# CAN_Funktionsdecoder.net
KiCad netlist of a schematic drawn in EAGLE
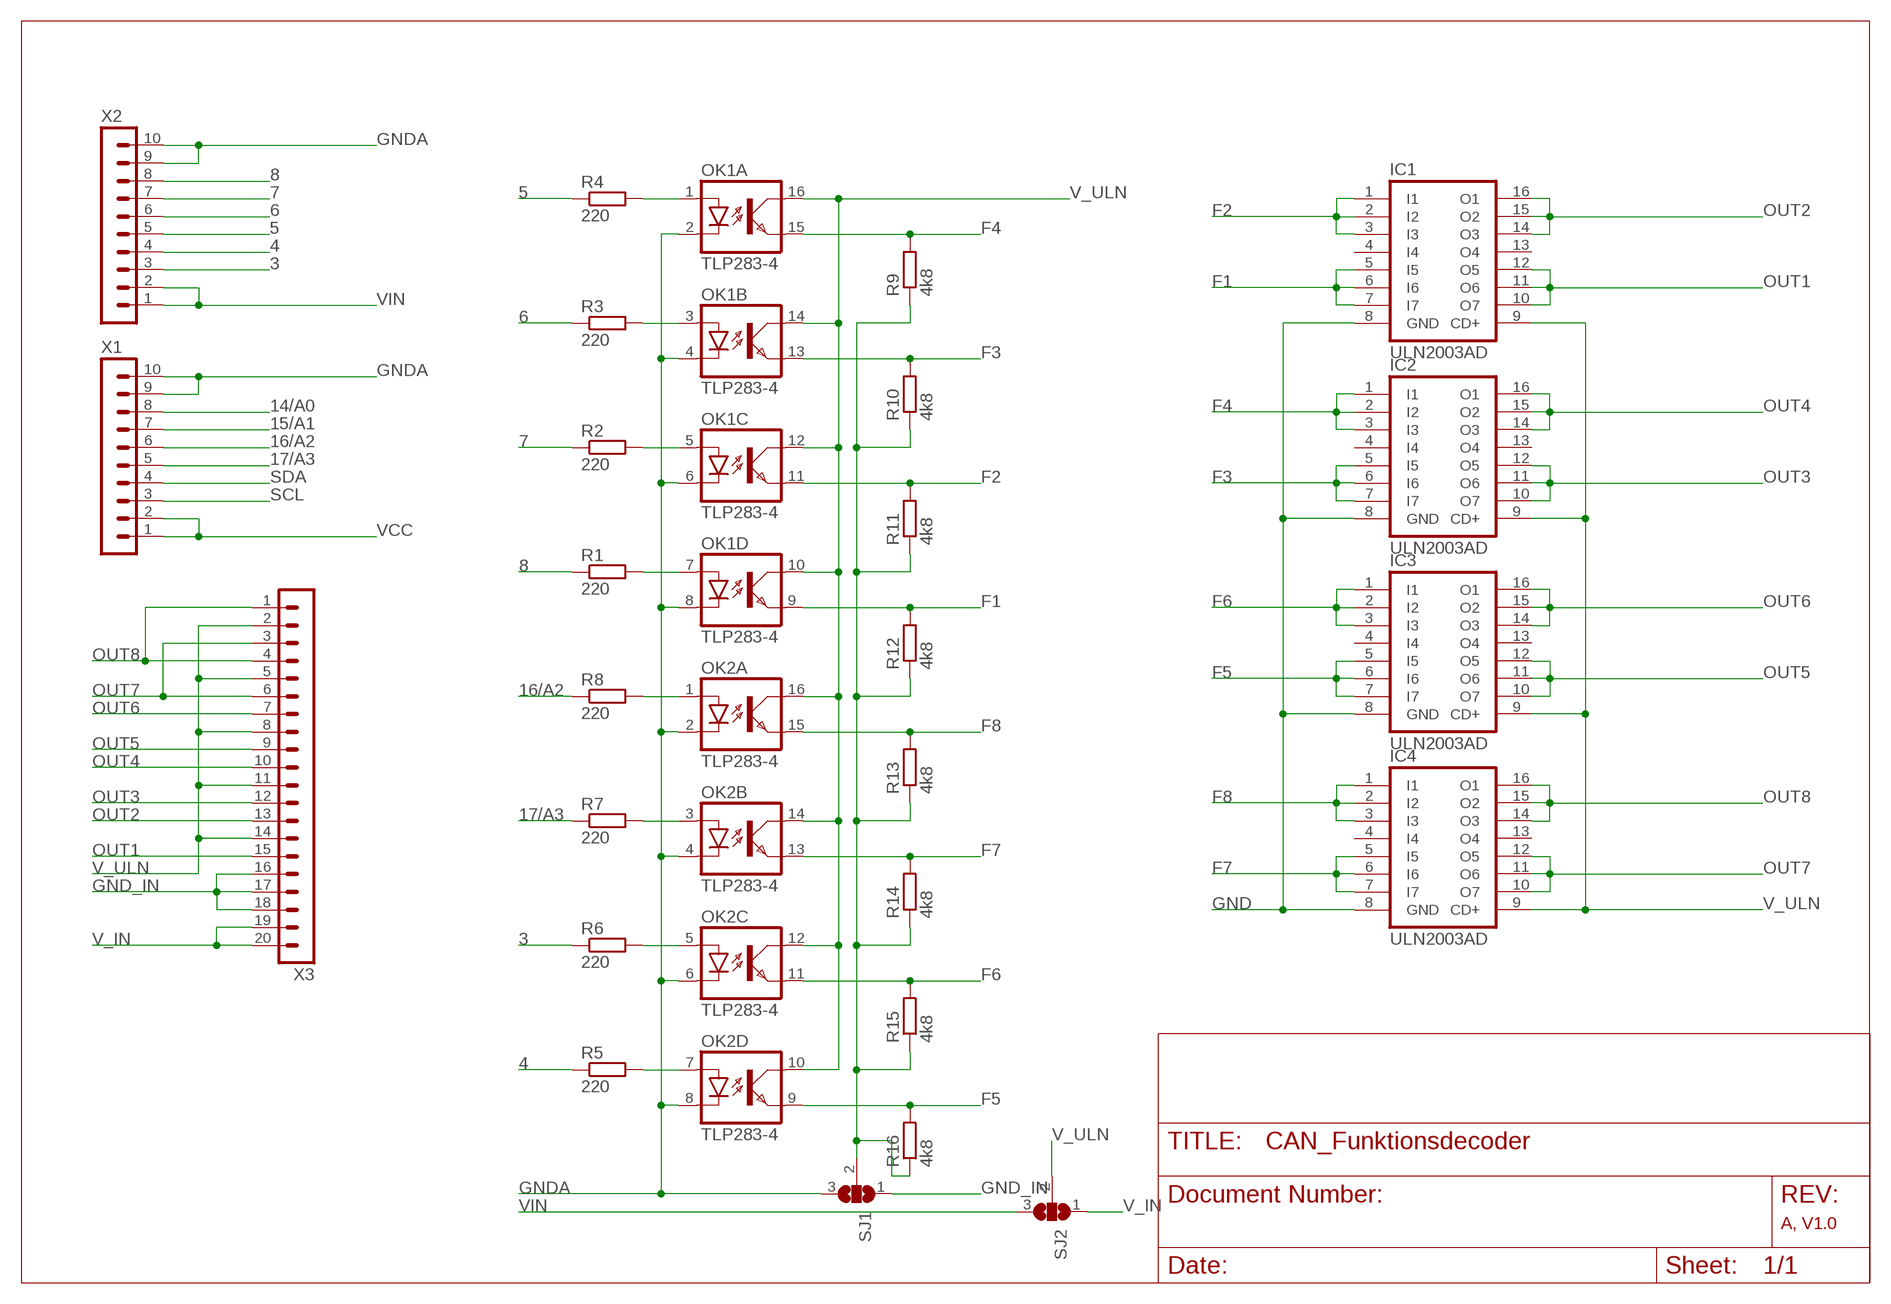
[diagram p0: schematic, sheet 1]

(export (version "E")
  (design (tool "Eeschema 10.0.6"))
  (components
    (comp (ref "IC1")
      (value "ULN2003AD")
      (footprint "eagle-import:SO16")
      (libsource (lib "eagle-import") (part "ULN2003AD"))
    )
    (comp (ref "IC2")
      (value "ULN2003AD")
      (footprint "eagle-import:SO16")
      (libsource (lib "eagle-import") (part "ULN2003AD"))
    )
    (comp (ref "IC3")
      (value "ULN2003AD")
      (footprint "eagle-import:SO16")
      (libsource (lib "eagle-import") (part "ULN2003AD"))
    )
    (comp (ref "IC4")
      (value "ULN2003AD")
      (footprint "eagle-import:SO16")
      (libsource (lib "eagle-import") (part "ULN2003AD"))
    )
    (comp (ref "OK1")
      (value "TLP283-4")
      (footprint "eagle-import:MINI-FLAT-16")
      (libsource (lib "eagle-import") (part "TLP283-4"))
    )
    (comp (ref "OK2")
      (value "TLP283-4")
      (footprint "eagle-import:MINI-FLAT-16")
      (libsource (lib "eagle-import") (part "TLP283-4"))
    )
    (comp (ref "R1")
      (value "220")
      (footprint "eagle-import:R0805")
      (libsource (lib "eagle-import") (part "R-EU_R0805"))
    )
    (comp (ref "R2")
      (value "220")
      (footprint "eagle-import:R0805")
      (libsource (lib "eagle-import") (part "R-EU_R0805"))
    )
    (comp (ref "R3")
      (value "220")
      (footprint "eagle-import:R0805")
      (libsource (lib "eagle-import") (part "R-EU_R0805"))
    )
    (comp (ref "R4")
      (value "220")
      (footprint "eagle-import:R0805")
      (libsource (lib "eagle-import") (part "R-EU_R0805"))
    )
    (comp (ref "R5")
      (value "220")
      (footprint "eagle-import:R0805")
      (libsource (lib "eagle-import") (part "R-EU_R0805"))
    )
    (comp (ref "R6")
      (value "220")
      (footprint "eagle-import:R0805")
      (libsource (lib "eagle-import") (part "R-EU_R0805"))
    )
    (comp (ref "R7")
      (value "220")
      (footprint "eagle-import:R0805")
      (libsource (lib "eagle-import") (part "R-EU_R0805"))
    )
    (comp (ref "R8")
      (value "220")
      (footprint "eagle-import:R0805")
      (libsource (lib "eagle-import") (part "R-EU_R0805"))
    )
    (comp (ref "R9")
      (value "4k8")
      (footprint "eagle-import:R0805")
      (libsource (lib "eagle-import") (part "R-EU_R0805"))
    )
    (comp (ref "R10")
      (value "4k8")
      (footprint "eagle-import:R0805")
      (libsource (lib "eagle-import") (part "R-EU_R0805"))
    )
    (comp (ref "R11")
      (value "4k8")
      (footprint "eagle-import:R0805")
      (libsource (lib "eagle-import") (part "R-EU_R0805"))
    )
    (comp (ref "R12")
      (value "4k8")
      (footprint "eagle-import:R0805")
      (libsource (lib "eagle-import") (part "R-EU_R0805"))
    )
    (comp (ref "R13")
      (value "4k8")
      (footprint "eagle-import:R0805")
      (libsource (lib "eagle-import") (part "R-EU_R0805"))
    )
    (comp (ref "R14")
      (value "4k8")
      (footprint "eagle-import:R0805")
      (libsource (lib "eagle-import") (part "R-EU_R0805"))
    )
    (comp (ref "R15")
      (value "4k8")
      (footprint "eagle-import:R0805")
      (libsource (lib "eagle-import") (part "R-EU_R0805"))
    )
    (comp (ref "R16")
      (value "4k8")
      (footprint "eagle-import:R0805")
      (libsource (lib "eagle-import") (part "R-EU_R0805"))
    )
    (comp (ref "SJ1")
      (value "SJ2W")
      (footprint "eagle-import:SJ_2")
      (libsource (lib "eagle-import") (part "SJ2W"))
    )
    (comp (ref "SJ2")
      (value "SJ2W")
      (footprint "eagle-import:SJ_2")
      (libsource (lib "eagle-import") (part "SJ2W"))
    )
    (comp (ref "X1")
      (value "MA10-1")
      (footprint "eagle-import:MA10-1")
      (libsource (lib "eagle-import") (part "MA10-1"))
    )
    (comp (ref "X2")
      (value "MA10-1")
      (footprint "eagle-import:MA10-1")
      (libsource (lib "eagle-import") (part "MA10-1"))
    )
    (comp (ref "X3")
      (value "MA20-1")
      (footprint "eagle-import:MA20-1")
      (libsource (lib "eagle-import") (part "MA20-1"))
    )
  )
  (nets
    (net (code "1") (name "/3") (class "Default")
      (node (ref "R6") (pin "1") (pinfunction "1_1") (pintype "passive"))
      (node (ref "X2") (pin "3") (pinfunction "3_3") (pintype "passive"))
    )
    (net (code "2") (name "/4") (class "Default")
      (node (ref "R5") (pin "1") (pinfunction "1_1") (pintype "passive"))
      (node (ref "X2") (pin "4") (pinfunction "4_4") (pintype "passive"))
    )
    (net (code "3") (name "/5") (class "Default")
      (node (ref "R4") (pin "1") (pinfunction "1_1") (pintype "passive"))
      (node (ref "X2") (pin "5") (pinfunction "5_5") (pintype "passive"))
    )
    (net (code "4") (name "/6") (class "Default")
      (node (ref "R3") (pin "1") (pinfunction "1_1") (pintype "passive"))
      (node (ref "X2") (pin "6") (pinfunction "6_6") (pintype "passive"))
    )
    (net (code "5") (name "/7") (class "Default")
      (node (ref "R2") (pin "1") (pinfunction "1_1") (pintype "passive"))
      (node (ref "X2") (pin "7") (pinfunction "7_7") (pintype "passive"))
    )
    (net (code "6") (name "/8") (class "Default")
      (node (ref "R1") (pin "1") (pinfunction "1_1") (pintype "passive"))
      (node (ref "X2") (pin "8") (pinfunction "8_8") (pintype "passive"))
    )
    (net (code "7") (name "/14{slash}A0") (class "Default")
      (node (ref "X1") (pin "8") (pinfunction "8_8") (pintype "passive"))
    )
    (net (code "8") (name "/15{slash}A1") (class "Default")
      (node (ref "X1") (pin "7") (pinfunction "7_7") (pintype "passive"))
    )
    (net (code "9") (name "/16{slash}A2") (class "Default")
      (node (ref "R8") (pin "1") (pinfunction "1_1") (pintype "passive"))
      (node (ref "X1") (pin "6") (pinfunction "6_6") (pintype "passive"))
    )
    (net (code "10") (name "/17{slash}A3") (class "Default")
      (node (ref "R7") (pin "1") (pinfunction "1_1") (pintype "passive"))
      (node (ref "X1") (pin "5") (pinfunction "5_5") (pintype "passive"))
    )
    (net (code "11") (name "/F1") (class "Default")
      (node (ref "IC1") (pin "5") (pinfunction "I5_5") (pintype "input"))
      (node (ref "IC1") (pin "6") (pinfunction "I6_6") (pintype "input"))
      (node (ref "IC1") (pin "7") (pinfunction "I7_7") (pintype "input"))
      (node (ref "OK1") (pin "9") (pinfunction "EMIT_9") (pintype "passive"))
      (node (ref "R12") (pin "2") (pinfunction "2_2") (pintype "passive"))
    )
    (net (code "12") (name "/F2") (class "Default")
      (node (ref "IC1") (pin "1") (pinfunction "I1_1") (pintype "input"))
      (node (ref "IC1") (pin "2") (pinfunction "I2_2") (pintype "input"))
      (node (ref "IC1") (pin "3") (pinfunction "I3_3") (pintype "input"))
      (node (ref "OK1") (pin "11") (pinfunction "EMIT_11") (pintype "passive"))
      (node (ref "R11") (pin "2") (pinfunction "2_2") (pintype "passive"))
    )
    (net (code "13") (name "/F3") (class "Default")
      (node (ref "IC2") (pin "5") (pinfunction "I5_5") (pintype "input"))
      (node (ref "IC2") (pin "6") (pinfunction "I6_6") (pintype "input"))
      (node (ref "IC2") (pin "7") (pinfunction "I7_7") (pintype "input"))
      (node (ref "OK1") (pin "13") (pinfunction "EMIT_13") (pintype "passive"))
      (node (ref "R10") (pin "2") (pinfunction "2_2") (pintype "passive"))
    )
    (net (code "14") (name "/F4") (class "Default")
      (node (ref "IC2") (pin "1") (pinfunction "I1_1") (pintype "input"))
      (node (ref "IC2") (pin "2") (pinfunction "I2_2") (pintype "input"))
      (node (ref "IC2") (pin "3") (pinfunction "I3_3") (pintype "input"))
      (node (ref "OK1") (pin "15") (pinfunction "EMIT_15") (pintype "passive"))
      (node (ref "R9") (pin "2") (pinfunction "2_2") (pintype "passive"))
    )
    (net (code "15") (name "/F5") (class "Default")
      (node (ref "IC3") (pin "5") (pinfunction "I5_5") (pintype "input"))
      (node (ref "IC3") (pin "6") (pinfunction "I6_6") (pintype "input"))
      (node (ref "IC3") (pin "7") (pinfunction "I7_7") (pintype "input"))
      (node (ref "OK2") (pin "9") (pinfunction "EMIT_9") (pintype "passive"))
      (node (ref "R16") (pin "2") (pinfunction "2_2") (pintype "passive"))
    )
    (net (code "16") (name "/F6") (class "Default")
      (node (ref "IC3") (pin "1") (pinfunction "I1_1") (pintype "input"))
      (node (ref "IC3") (pin "2") (pinfunction "I2_2") (pintype "input"))
      (node (ref "IC3") (pin "3") (pinfunction "I3_3") (pintype "input"))
      (node (ref "OK2") (pin "11") (pinfunction "EMIT_11") (pintype "passive"))
      (node (ref "R15") (pin "2") (pinfunction "2_2") (pintype "passive"))
    )
    (net (code "17") (name "/F7") (class "Default")
      (node (ref "IC4") (pin "5") (pinfunction "I5_5") (pintype "input"))
      (node (ref "IC4") (pin "6") (pinfunction "I6_6") (pintype "input"))
      (node (ref "IC4") (pin "7") (pinfunction "I7_7") (pintype "input"))
      (node (ref "OK2") (pin "13") (pinfunction "EMIT_13") (pintype "passive"))
      (node (ref "R14") (pin "2") (pinfunction "2_2") (pintype "passive"))
    )
    (net (code "18") (name "/F8") (class "Default")
      (node (ref "IC4") (pin "1") (pinfunction "I1_1") (pintype "input"))
      (node (ref "IC4") (pin "2") (pinfunction "I2_2") (pintype "input"))
      (node (ref "IC4") (pin "3") (pinfunction "I3_3") (pintype "input"))
      (node (ref "OK2") (pin "15") (pinfunction "EMIT_15") (pintype "passive"))
      (node (ref "R13") (pin "2") (pinfunction "2_2") (pintype "passive"))
    )
    (net (code "19") (name "/GND") (class "Default")
      (node (ref "IC1") (pin "8") (pinfunction "GND_8") (pintype "power_in"))
      (node (ref "IC2") (pin "8") (pinfunction "GND_8") (pintype "power_in"))
      (node (ref "IC3") (pin "8") (pinfunction "GND_8") (pintype "power_in"))
      (node (ref "IC4") (pin "8") (pinfunction "GND_8") (pintype "power_in"))
      (node (ref "R10") (pin "1") (pinfunction "1_1") (pintype "passive"))
      (node (ref "R11") (pin "1") (pinfunction "1_1") (pintype "passive"))
      (node (ref "R12") (pin "1") (pinfunction "1_1") (pintype "passive"))
      (node (ref "R13") (pin "1") (pinfunction "1_1") (pintype "passive"))
      (node (ref "R14") (pin "1") (pinfunction "1_1") (pintype "passive"))
      (node (ref "R15") (pin "1") (pinfunction "1_1") (pintype "passive"))
      (node (ref "R16") (pin "1") (pinfunction "1_1") (pintype "passive"))
      (node (ref "R9") (pin "1") (pinfunction "1_1") (pintype "passive"))
      (node (ref "SJ1") (pin "2") (pinfunction "2_2") (pintype "passive"))
    )
    (net (code "20") (name "/GNDA") (class "Default")
      (node (ref "OK1") (pin "2") (pinfunction "C_2") (pintype "passive"))
      (node (ref "OK1") (pin "4") (pinfunction "C_4") (pintype "passive"))
      (node (ref "OK1") (pin "6") (pinfunction "C_6") (pintype "passive"))
      (node (ref "OK1") (pin "8") (pinfunction "C_8") (pintype "passive"))
      (node (ref "OK2") (pin "2") (pinfunction "C_2") (pintype "passive"))
      (node (ref "OK2") (pin "4") (pinfunction "C_4") (pintype "passive"))
      (node (ref "OK2") (pin "6") (pinfunction "C_6") (pintype "passive"))
      (node (ref "OK2") (pin "8") (pinfunction "C_8") (pintype "passive"))
      (node (ref "SJ1") (pin "3") (pinfunction "3_3") (pintype "passive"))
      (node (ref "X1") (pin "10") (pinfunction "10_10") (pintype "passive"))
      (node (ref "X1") (pin "9") (pinfunction "9_9") (pintype "passive"))
      (node (ref "X2") (pin "10") (pinfunction "10_10") (pintype "passive"))
      (node (ref "X2") (pin "9") (pinfunction "9_9") (pintype "passive"))
    )
    (net (code "21") (name "/GND_IN") (class "Default")
      (node (ref "SJ1") (pin "1") (pinfunction "1_1") (pintype "passive"))
      (node (ref "X3") (pin "16") (pinfunction "16_16") (pintype "passive"))
      (node (ref "X3") (pin "17") (pinfunction "17_17") (pintype "passive"))
      (node (ref "X3") (pin "18") (pinfunction "18_18") (pintype "passive"))
    )
    (net (code "22") (name "/OUT1") (class "Default")
      (node (ref "IC1") (pin "10") (pinfunction "O7_10") (pintype "open_collector"))
      (node (ref "IC1") (pin "11") (pinfunction "O6_11") (pintype "open_collector"))
      (node (ref "IC1") (pin "12") (pinfunction "O5_12") (pintype "open_collector"))
      (node (ref "X3") (pin "15") (pinfunction "15_15") (pintype "passive"))
    )
    (net (code "23") (name "/OUT2") (class "Default")
      (node (ref "IC1") (pin "14") (pinfunction "O3_14") (pintype "open_collector"))
      (node (ref "IC1") (pin "15") (pinfunction "O2_15") (pintype "open_collector"))
      (node (ref "IC1") (pin "16") (pinfunction "O1_16") (pintype "open_collector"))
      (node (ref "X3") (pin "13") (pinfunction "13_13") (pintype "passive"))
    )
    (net (code "24") (name "/OUT3") (class "Default")
      (node (ref "IC2") (pin "10") (pinfunction "O7_10") (pintype "open_collector"))
      (node (ref "IC2") (pin "11") (pinfunction "O6_11") (pintype "open_collector"))
      (node (ref "IC2") (pin "12") (pinfunction "O5_12") (pintype "open_collector"))
      (node (ref "X3") (pin "12") (pinfunction "12_12") (pintype "passive"))
    )
    (net (code "25") (name "/OUT4") (class "Default")
      (node (ref "IC2") (pin "14") (pinfunction "O3_14") (pintype "open_collector"))
      (node (ref "IC2") (pin "15") (pinfunction "O2_15") (pintype "open_collector"))
      (node (ref "IC2") (pin "16") (pinfunction "O1_16") (pintype "open_collector"))
      (node (ref "X3") (pin "10") (pinfunction "10_10") (pintype "passive"))
    )
    (net (code "26") (name "/OUT5") (class "Default")
      (node (ref "IC3") (pin "10") (pinfunction "O7_10") (pintype "open_collector"))
      (node (ref "IC3") (pin "11") (pinfunction "O6_11") (pintype "open_collector"))
      (node (ref "IC3") (pin "12") (pinfunction "O5_12") (pintype "open_collector"))
      (node (ref "X3") (pin "9") (pinfunction "9_9") (pintype "passive"))
    )
    (net (code "27") (name "/OUT6") (class "Default")
      (node (ref "IC3") (pin "14") (pinfunction "O3_14") (pintype "open_collector"))
      (node (ref "IC3") (pin "15") (pinfunction "O2_15") (pintype "open_collector"))
      (node (ref "IC3") (pin "16") (pinfunction "O1_16") (pintype "open_collector"))
      (node (ref "X3") (pin "7") (pinfunction "7_7") (pintype "passive"))
    )
    (net (code "28") (name "/OUT7") (class "Default")
      (node (ref "IC4") (pin "10") (pinfunction "O7_10") (pintype "open_collector"))
      (node (ref "IC4") (pin "11") (pinfunction "O6_11") (pintype "open_collector"))
      (node (ref "IC4") (pin "12") (pinfunction "O5_12") (pintype "open_collector"))
      (node (ref "X3") (pin "3") (pinfunction "3_3") (pintype "passive"))
      (node (ref "X3") (pin "6") (pinfunction "6_6") (pintype "passive"))
    )
    (net (code "29") (name "/OUT8") (class "Default")
      (node (ref "IC4") (pin "14") (pinfunction "O3_14") (pintype "open_collector"))
      (node (ref "IC4") (pin "15") (pinfunction "O2_15") (pintype "open_collector"))
      (node (ref "IC4") (pin "16") (pinfunction "O1_16") (pintype "open_collector"))
      (node (ref "X3") (pin "1") (pinfunction "1_1") (pintype "passive"))
      (node (ref "X3") (pin "4") (pinfunction "4_4") (pintype "passive"))
    )
    (net (code "30") (name "/SCL") (class "Default")
      (node (ref "X1") (pin "3") (pinfunction "3_3") (pintype "passive"))
    )
    (net (code "31") (name "/SDA") (class "Default")
      (node (ref "X1") (pin "4") (pinfunction "4_4") (pintype "passive"))
    )
    (net (code "32") (name "/VCC") (class "Default")
      (node (ref "X1") (pin "1") (pinfunction "1_1") (pintype "passive"))
      (node (ref "X1") (pin "2") (pinfunction "2_2") (pintype "passive"))
    )
    (net (code "33") (name "/VIN") (class "Default")
      (node (ref "SJ2") (pin "3") (pinfunction "3_3") (pintype "passive"))
      (node (ref "X2") (pin "1") (pinfunction "1_1") (pintype "passive"))
      (node (ref "X2") (pin "2") (pinfunction "2_2") (pintype "passive"))
    )
    (net (code "34") (name "/V_IN") (class "Default")
      (node (ref "SJ2") (pin "1") (pinfunction "1_1") (pintype "passive"))
      (node (ref "X3") (pin "19") (pinfunction "19_19") (pintype "passive"))
      (node (ref "X3") (pin "20") (pinfunction "20_20") (pintype "passive"))
    )
    (net (code "35") (name "/V_ULN") (class "Default")
      (node (ref "IC1") (pin "9") (pinfunction "CD+_9") (pintype "passive"))
      (node (ref "IC2") (pin "9") (pinfunction "CD+_9") (pintype "passive"))
      (node (ref "IC3") (pin "9") (pinfunction "CD+_9") (pintype "passive"))
      (node (ref "IC4") (pin "9") (pinfunction "CD+_9") (pintype "passive"))
      (node (ref "OK1") (pin "10") (pinfunction "COL_10") (pintype "passive"))
      (node (ref "OK1") (pin "12") (pinfunction "COL_12") (pintype "passive"))
      (node (ref "OK1") (pin "14") (pinfunction "COL_14") (pintype "passive"))
      (node (ref "OK1") (pin "16") (pinfunction "COL_16") (pintype "passive"))
      (node (ref "OK2") (pin "10") (pinfunction "COL_10") (pintype "passive"))
      (node (ref "OK2") (pin "12") (pinfunction "COL_12") (pintype "passive"))
      (node (ref "OK2") (pin "14") (pinfunction "COL_14") (pintype "passive"))
      (node (ref "OK2") (pin "16") (pinfunction "COL_16") (pintype "passive"))
      (node (ref "SJ2") (pin "2") (pinfunction "2_2") (pintype "passive"))
      (node (ref "X3") (pin "11") (pinfunction "11_11") (pintype "passive"))
      (node (ref "X3") (pin "14") (pinfunction "14_14") (pintype "passive"))
      (node (ref "X3") (pin "2") (pinfunction "2_2") (pintype "passive"))
      (node (ref "X3") (pin "5") (pinfunction "5_5") (pintype "passive"))
      (node (ref "X3") (pin "8") (pinfunction "8_8") (pintype "passive"))
    )
    (net (code "36") (name "Net-(OK1A-A)") (class "Default")
      (node (ref "OK1") (pin "1") (pinfunction "A_1") (pintype "passive"))
      (node (ref "R4") (pin "2") (pinfunction "2_2") (pintype "passive"))
    )
    (net (code "37") (name "Net-(OK1B-A)") (class "Default")
      (node (ref "OK1") (pin "3") (pinfunction "A_3") (pintype "passive"))
      (node (ref "R3") (pin "2") (pinfunction "2_2") (pintype "passive"))
    )
    (net (code "38") (name "Net-(OK1C-A)") (class "Default")
      (node (ref "OK1") (pin "5") (pinfunction "A_5") (pintype "passive"))
      (node (ref "R2") (pin "2") (pinfunction "2_2") (pintype "passive"))
    )
    (net (code "39") (name "Net-(OK1D-A)") (class "Default")
      (node (ref "OK1") (pin "7") (pinfunction "A_7") (pintype "passive"))
      (node (ref "R1") (pin "2") (pinfunction "2_2") (pintype "passive"))
    )
    (net (code "40") (name "Net-(OK2A-A)") (class "Default")
      (node (ref "OK2") (pin "1") (pinfunction "A_1") (pintype "passive"))
      (node (ref "R8") (pin "2") (pinfunction "2_2") (pintype "passive"))
    )
    (net (code "41") (name "Net-(OK2B-A)") (class "Default")
      (node (ref "OK2") (pin "3") (pinfunction "A_3") (pintype "passive"))
      (node (ref "R7") (pin "2") (pinfunction "2_2") (pintype "passive"))
    )
    (net (code "42") (name "Net-(OK2C-A)") (class "Default")
      (node (ref "OK2") (pin "5") (pinfunction "A_5") (pintype "passive"))
      (node (ref "R6") (pin "2") (pinfunction "2_2") (pintype "passive"))
    )
    (net (code "43") (name "Net-(OK2D-A)") (class "Default")
      (node (ref "OK2") (pin "7") (pinfunction "A_7") (pintype "passive"))
      (node (ref "R5") (pin "2") (pinfunction "2_2") (pintype "passive"))
    )
    (net (code "44") (name "unconnected-(IC1-I4-Pad4)") (class "Default")
      (node (ref "IC1") (pin "4") (pinfunction "I4_4") (pintype "input"))
    )
    (net (code "45") (name "unconnected-(IC1-O4-Pad13)") (class "Default")
      (node (ref "IC1") (pin "13") (pinfunction "O4_13") (pintype "open_collector"))
    )
    (net (code "46") (name "unconnected-(IC2-I4-Pad4)") (class "Default")
      (node (ref "IC2") (pin "4") (pinfunction "I4_4") (pintype "input"))
    )
    (net (code "47") (name "unconnected-(IC2-O4-Pad13)") (class "Default")
      (node (ref "IC2") (pin "13") (pinfunction "O4_13") (pintype "open_collector"))
    )
    (net (code "48") (name "unconnected-(IC3-I4-Pad4)") (class "Default")
      (node (ref "IC3") (pin "4") (pinfunction "I4_4") (pintype "input"))
    )
    (net (code "49") (name "unconnected-(IC3-O4-Pad13)") (class "Default")
      (node (ref "IC3") (pin "13") (pinfunction "O4_13") (pintype "open_collector"))
    )
    (net (code "50") (name "unconnected-(IC4-I4-Pad4)") (class "Default")
      (node (ref "IC4") (pin "4") (pinfunction "I4_4") (pintype "input"))
    )
    (net (code "51") (name "unconnected-(IC4-O4-Pad13)") (class "Default")
      (node (ref "IC4") (pin "13") (pinfunction "O4_13") (pintype "open_collector"))
    )
  )
)
